# LowSideSupply.net
KiCad netlist of a schematic drawn in Altium Designer
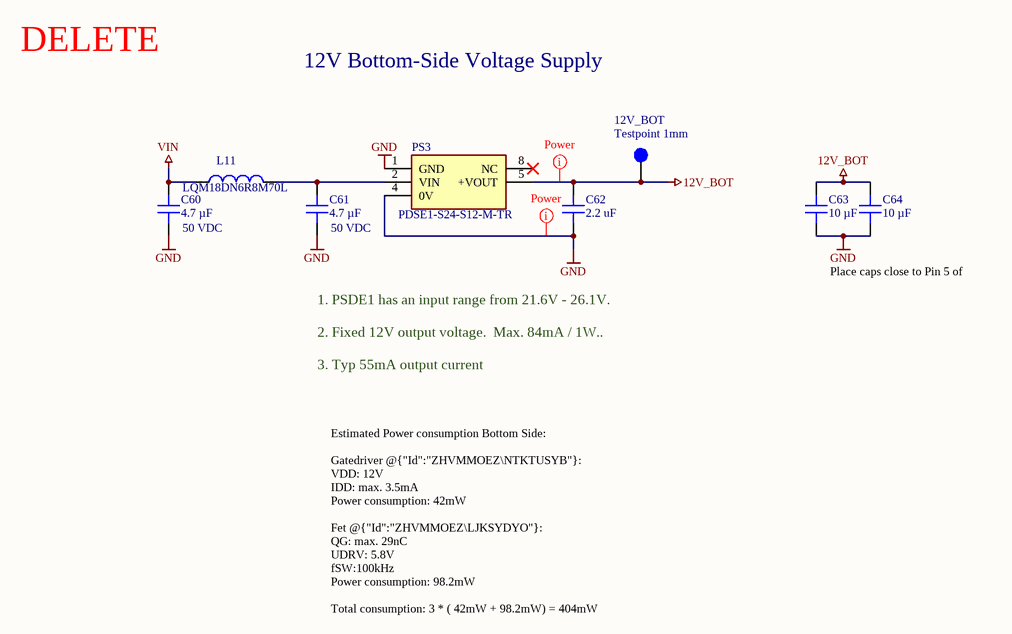
[diagram p0: LowSideSupply.SchDoc]

(export (version "E")
  (design (tool "Eeschema 10.0.6"))
  (components
    (comp (ref "12V_BOT")
      (value "Testpoint 1mm")
      (footprint "TP_1mm")
      (fields
        (field (name "MANUFACTURER PART NUMBER") "NULL")
        (field (name "CREATED") "2018_06_25_AGeiger")
        (field (name "CREATED FROM") "AGeiger")
      )
      (libsource (lib "user") (part "TP_1mm"))
    )
    (comp (ref "C60")
      (value "4.7 µF")
      (footprint "C_0805")
      (description "Capacitor 0805, 50 VDC, 4.7 µF, X7R")
      (fields
        (field (name "MANUFACTURER PART NUMBER") "C2012X7R1H475K125AC")
        (field (name "MANUFACTURER") "TDK")
        (field (name "VOLTAGE RATING") "50 VDC")
        (field (name "CREATED FROM") "MGremer")
      )
      (libsource (lib "user") (part "Capacitor"))
    )
    (comp (ref "C61")
      (value "4.7 µF")
      (footprint "C_0805")
      (description "Capacitor 0805, 50 VDC, 4.7 µF, X7R")
      (fields
        (field (name "MANUFACTURER PART NUMBER") "C2012X7R1H475K125AC")
        (field (name "MANUFACTURER") "TDK")
        (field (name "VOLTAGE RATING") "50 VDC")
        (field (name "CREATED FROM") "MGremer")
      )
      (libsource (lib "user") (part "Capacitor"))
    )
    (comp (ref "C62")
      (value "2.2 uF")
      (footprint "C_0603")
      (description "Capacitor 0603, 25 VDC, 2.2 uF, X5R")
      (fields
        (field (name "MANUFACTURER PART NUMBER") "C1608X5R1E225K080AB")
        (field (name "MANUFACTURER") "TDK")
        (field (name "CREATED FROM") "DHufnagel")
      )
      (libsource (lib "user") (part "Capacitor"))
    )
    (comp (ref "C63")
      (value "10 µF")
      (footprint "C_1210_N")
      (description "Capacitor 1210, 100 VDC, 10µF, X7S")
      (fields
        (field (name "MANUFACTURER PART NUMBER") "GRM32EC72A106KE05L")
        (field (name "MANUFACTURER") "Murata Electronics")
        (field (name "CREATED FROM") "DHufnagel")
      )
      (libsource (lib "user") (part "Capacitor"))
    )
    (comp (ref "C64")
      (value "10 µF")
      (footprint "C_1210_N")
      (description "Capacitor 1210, 100 VDC, 10µF, X7S")
      (fields
        (field (name "MANUFACTURER PART NUMBER") "GRM32EC72A106KE05L")
        (field (name "MANUFACTURER") "Murata Electronics")
        (field (name "CREATED FROM") "DHufnagel")
      )
      (libsource (lib "user") (part "Capacitor"))
    )
    (comp (ref "L11")
      (value "LQM18DN6R8M70L")
      (footprint "INDC1608X95N")
      (description "6.8µH, 120mA, 0603, 740mOhm, 20%")
      (fields
        (field (name "MF") "EPCOS / TDK")
        (field (name "MPN") "B82464G4154M")
        (field (name "CREATED FROM") "DHufnagel")
      )
      (libsource (lib "user") (part "B82464G4154M"))
    )
    (comp (ref "PS3")
      (value "PDSE1-S24-S12-M-TR")
      (footprint "PDSE1S24S12MTR")
      (description "Isolated, 21.6 -26.4Vin, 12V out, 1W, 84mA out")
      (fields (field (name "MANUFACTURER") "CUI Inc.") (field (name "CREATED FROM") "DHufnagel"))
      (libsource (lib "user") (part "PDSE1-S24-S12-M-TR"))
    )
  )
  (nets
    (net (code "1") (name "12V_BOT") (class "Default")
      (node (ref "12V_BOT") (pin "1") (pintype "passive"))
      (node (ref "C62") (pin "2") (pinfunction "2_2") (pintype "passive"))
      (node (ref "C63") (pin "2") (pinfunction "2_2") (pintype "passive"))
      (node (ref "C64") (pin "2") (pinfunction "2_2") (pintype "passive"))
      (node (ref "PS3") (pin "5") (pinfunction "+VOUT_5") (pintype "passive"))
    )
    (net (code "2") (name "GND") (class "Default")
      (node (ref "C60") (pin "2") (pinfunction "2_2") (pintype "passive"))
      (node (ref "C61") (pin "2") (pinfunction "2_2") (pintype "passive"))
      (node (ref "C62") (pin "1") (pinfunction "1_1") (pintype "passive"))
      (node (ref "C63") (pin "1") (pinfunction "1_1") (pintype "passive"))
      (node (ref "C64") (pin "1") (pinfunction "1_1") (pintype "passive"))
      (node (ref "PS3") (pin "1") (pinfunction "GND_1") (pintype "passive"))
      (node (ref "PS3") (pin "4") (pinfunction "0V_4") (pintype "passive"))
    )
    (net (code "3") (name "Net-(PS3-VIN)") (class "Default")
      (node (ref "C61") (pin "1") (pinfunction "1_1") (pintype "passive"))
      (node (ref "L11") (pin "2") (pinfunction "2_2") (pintype "passive"))
      (node (ref "PS3") (pin "2") (pinfunction "VIN_2") (pintype "passive"))
    )
    (net (code "4") (name "VIN") (class "Default")
      (node (ref "C60") (pin "1") (pinfunction "1_1") (pintype "passive"))
      (node (ref "L11") (pin "1") (pinfunction "1_1") (pintype "passive"))
    )
    (net (code "5") (name "unconnected-(PS3-NC-Pad8)") (class "Default")
      (node (ref "PS3") (pin "8") (pinfunction "NC_8") (pintype "passive+no_connect"))
    )
  )
)
